# MX.net
KiCad netlist of a schematic drawn in Altium Designer
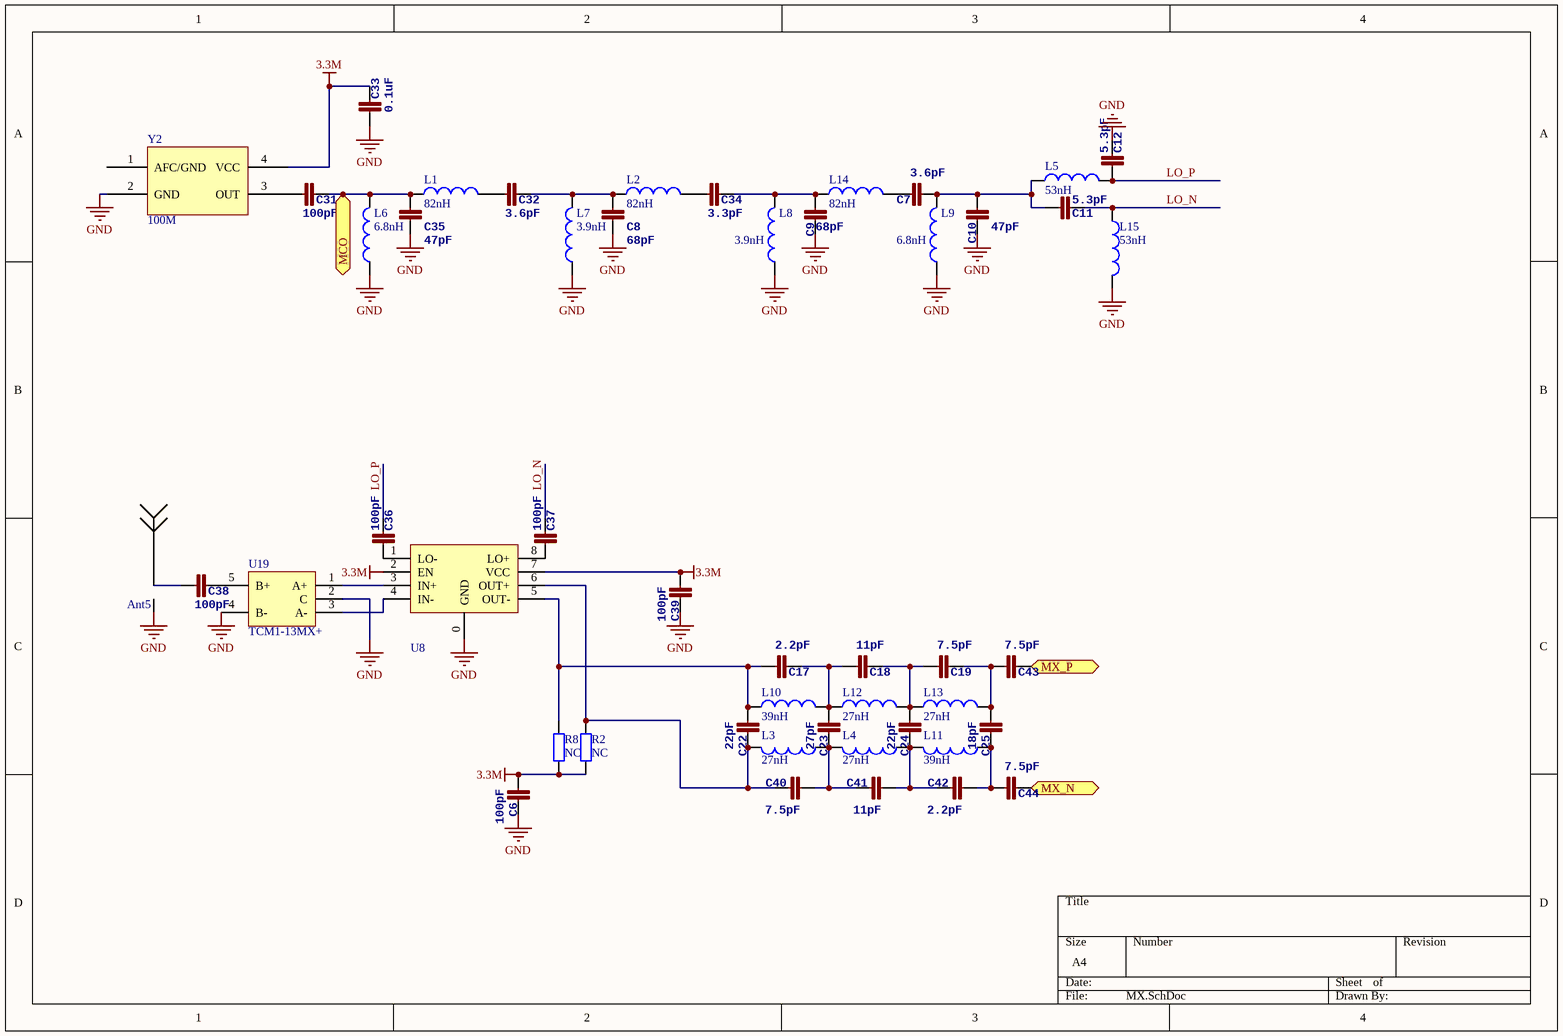
[diagram p0: MX.SchDoc]

(export (version "E")
  (design (tool "Eeschema 10.0.6"))
  (components
    (comp (ref "Ant5") (value "Antenna") (footprint "BK5811:SMA") (libsource (lib "F4SDR") (part "Antenna")))
    (comp (ref "C6")
      (value "100pF")
      (footprint "0402")
      (description "<b>Capacitor</b>\nStandard 0603 ceramic capacitor, and 0.1\" leaded capacitor.")
      (fields (field (name "PARTNO") "CC0402ZRY5V7BB104"))
      (libsource (lib "") (part "CAP0402-CAP_1"))
    )
    (comp (ref "C7")
      (value "3.6pF")
      (footprint "0402")
      (description "<b>Capacitor</b>\nStandard 0603 ceramic capacitor, and 0.1\" leaded capacitor.")
      (fields (field (name "PARTNO") "CC0402ZRY5V7BB104"))
      (libsource (lib "pixhawk2") (part "CAP0402-CAP"))
    )
    (comp (ref "C8")
      (value "68pF")
      (footprint "0402")
      (description "<b>Capacitor</b>\nStandard 0603 ceramic capacitor, and 0.1\" leaded capacitor.")
      (fields (field (name "PARTNO") "CC0402ZRY5V7BB104"))
      (libsource (lib "") (part "CAP0402-CAP_1"))
    )
    (comp (ref "C9")
      (value "68pF")
      (footprint "0402")
      (description "<b>Capacitor</b>\nStandard 0603 ceramic capacitor, and 0.1\" leaded capacitor.")
      (fields (field (name "PARTNO") "CC0402ZRY5V7BB104"))
      (libsource (lib "") (part "CAP0402-CAP_1"))
    )
    (comp (ref "C10")
      (value "47pF")
      (footprint "0402")
      (description "<b>Capacitor</b>\nStandard 0603 ceramic capacitor, and 0.1\" leaded capacitor.")
      (fields (field (name "PARTNO") "CC0402ZRY5V7BB104"))
      (libsource (lib "") (part "CAP0402-CAP_1"))
    )
    (comp (ref "C11")
      (value "5.3pF")
      (footprint "0402")
      (description "<b>Capacitor</b>\nStandard 0603 ceramic capacitor, and 0.1\" leaded capacitor.")
      (fields (field (name "PARTNO") "CC0402ZRY5V7BB104"))
      (libsource (lib "pixhawk2") (part "CAP0402-CAP"))
    )
    (comp (ref "C12")
      (value "5.3pF")
      (footprint "0402")
      (description "<b>Capacitor</b>\nStandard 0603 ceramic capacitor, and 0.1\" leaded capacitor.")
      (fields (field (name "PARTNO") "CC0402ZRY5V7BB104"))
      (libsource (lib "") (part "CAP0402-CAP_2"))
    )
    (comp (ref "C17")
      (value "2.2pF")
      (footprint "0402")
      (description "<b>Capacitor</b>\nStandard 0603 ceramic capacitor, and 0.1\" leaded capacitor.")
      (fields (field (name "PARTNO") "CC0402ZRY5V7BB104"))
      (libsource (lib "pixhawk2") (part "CAP0402-CAP"))
    )
    (comp (ref "C18")
      (value "11pF")
      (footprint "0402")
      (description "<b>Capacitor</b>\nStandard 0603 ceramic capacitor, and 0.1\" leaded capacitor.")
      (fields (field (name "PARTNO") "CC0402ZRY5V7BB104"))
      (libsource (lib "pixhawk2") (part "CAP0402-CAP"))
    )
    (comp (ref "C19")
      (value "7.5pF")
      (footprint "0402")
      (description "<b>Capacitor</b>\nStandard 0603 ceramic capacitor, and 0.1\" leaded capacitor.")
      (fields (field (name "PARTNO") "CC0402ZRY5V7BB104"))
      (libsource (lib "pixhawk2") (part "CAP0402-CAP"))
    )
    (comp (ref "C22")
      (value "22pF")
      (footprint "0402")
      (description "<b>Capacitor</b>\nStandard 0603 ceramic capacitor, and 0.1\" leaded capacitor.")
      (fields (field (name "PARTNO") "CC0402ZRY5V7BB104"))
      (libsource (lib "") (part "CAP0402-CAP_1"))
    )
    (comp (ref "C23")
      (value "27pF")
      (footprint "0402")
      (description "<b>Capacitor</b>\nStandard 0603 ceramic capacitor, and 0.1\" leaded capacitor.")
      (fields (field (name "PARTNO") "CC0402ZRY5V7BB104"))
      (libsource (lib "") (part "CAP0402-CAP_1"))
    )
    (comp (ref "C24")
      (value "22pF")
      (footprint "0402")
      (description "<b>Capacitor</b>\nStandard 0603 ceramic capacitor, and 0.1\" leaded capacitor.")
      (fields (field (name "PARTNO") "CC0402ZRY5V7BB104"))
      (libsource (lib "") (part "CAP0402-CAP_1"))
    )
    (comp (ref "C25")
      (value "18pF")
      (footprint "0402")
      (description "<b>Capacitor</b>\nStandard 0603 ceramic capacitor, and 0.1\" leaded capacitor.")
      (fields (field (name "PARTNO") "CC0402ZRY5V7BB104"))
      (libsource (lib "") (part "CAP0402-CAP_1"))
    )
    (comp (ref "C31")
      (value "100pF")
      (footprint "0402")
      (description "<b>Capacitor</b>\nStandard 0603 ceramic capacitor, and 0.1\" leaded capacitor.")
      (fields (field (name "PARTNO") "CC0402ZRY5V7BB104"))
      (libsource (lib "pixhawk2") (part "CAP0402-CAP"))
    )
    (comp (ref "C32")
      (value "3.6pF")
      (footprint "0402")
      (description "<b>Capacitor</b>\nStandard 0603 ceramic capacitor, and 0.1\" leaded capacitor.")
      (fields (field (name "PARTNO") "CC0402ZRY5V7BB104"))
      (libsource (lib "pixhawk2") (part "CAP0402-CAP"))
    )
    (comp (ref "C33")
      (value "0.1uF")
      (footprint "0402")
      (description "<b>Capacitor</b>\nStandard 0603 ceramic capacitor, and 0.1\" leaded capacitor.")
      (fields (field (name "PARTNO") "CC0402ZRY5V7BB104"))
      (libsource (lib "") (part "CAP0402-CAP_2"))
    )
    (comp (ref "C34")
      (value "3.3pF")
      (footprint "0402")
      (description "<b>Capacitor</b>\nStandard 0603 ceramic capacitor, and 0.1\" leaded capacitor.")
      (fields (field (name "PARTNO") "CC0402ZRY5V7BB104"))
      (libsource (lib "pixhawk2") (part "CAP0402-CAP"))
    )
    (comp (ref "C35")
      (value "47pF")
      (footprint "0402")
      (description "<b>Capacitor</b>\nStandard 0603 ceramic capacitor, and 0.1\" leaded capacitor.")
      (fields (field (name "PARTNO") "CC0402ZRY5V7BB104"))
      (libsource (lib "") (part "CAP0402-CAP_1"))
    )
    (comp (ref "C36")
      (value "100pF")
      (footprint "0402")
      (description "<b>Capacitor</b>\nStandard 0603 ceramic capacitor, and 0.1\" leaded capacitor.")
      (fields (field (name "PARTNO") "CC0402ZRY5V7BB104"))
      (libsource (lib "") (part "CAP0402-CAP_2"))
    )
    (comp (ref "C37")
      (value "100pF")
      (footprint "0402")
      (description "<b>Capacitor</b>\nStandard 0603 ceramic capacitor, and 0.1\" leaded capacitor.")
      (fields (field (name "PARTNO") "CC0402ZRY5V7BB104"))
      (libsource (lib "") (part "CAP0402-CAP_2"))
    )
    (comp (ref "C38")
      (value "100pF")
      (footprint "0402")
      (description "<b>Capacitor</b>\nStandard 0603 ceramic capacitor, and 0.1\" leaded capacitor.")
      (fields (field (name "PARTNO") "CC0402ZRY5V7BB104"))
      (libsource (lib "pixhawk2") (part "CAP0402-CAP"))
    )
    (comp (ref "C39")
      (value "100pF")
      (footprint "0402")
      (description "<b>Capacitor</b>\nStandard 0603 ceramic capacitor, and 0.1\" leaded capacitor.")
      (fields (field (name "PARTNO") "CC0402ZRY5V7BB104"))
      (libsource (lib "") (part "CAP0402-CAP_1"))
    )
    (comp (ref "C40")
      (value "7.5pF")
      (footprint "0402")
      (description "<b>Capacitor</b>\nStandard 0603 ceramic capacitor, and 0.1\" leaded capacitor.")
      (fields (field (name "PARTNO") "CC0402ZRY5V7BB104"))
      (libsource (lib "") (part "CAP0402-CAP_3"))
    )
    (comp (ref "C41")
      (value "11pF")
      (footprint "0402")
      (description "<b>Capacitor</b>\nStandard 0603 ceramic capacitor, and 0.1\" leaded capacitor.")
      (fields (field (name "PARTNO") "CC0402ZRY5V7BB104"))
      (libsource (lib "") (part "CAP0402-CAP_3"))
    )
    (comp (ref "C42")
      (value "2.2pF")
      (footprint "0402")
      (description "<b>Capacitor</b>\nStandard 0603 ceramic capacitor, and 0.1\" leaded capacitor.")
      (fields (field (name "PARTNO") "CC0402ZRY5V7BB104"))
      (libsource (lib "") (part "CAP0402-CAP_3"))
    )
    (comp (ref "C43")
      (value "7.5pF")
      (footprint "0402")
      (description "<b>Capacitor</b>\nStandard 0603 ceramic capacitor, and 0.1\" leaded capacitor.")
      (fields (field (name "PARTNO") "CC0402ZRY5V7BB104"))
      (libsource (lib "pixhawk2") (part "CAP0402-CAP"))
    )
    (comp (ref "C44")
      (value "7.5pF")
      (footprint "0402")
      (description "<b>Capacitor</b>\nStandard 0603 ceramic capacitor, and 0.1\" leaded capacitor.")
      (fields (field (name "PARTNO") "CC0402ZRY5V7BB104"))
      (libsource (lib "pixhawk2") (part "CAP0402-CAP"))
    )
    (comp (ref "L1")
      (value "82nH")
      (footprint "0402")
      (description "Inductor")
      (fields (field (name "PUBLISHER") "Altium Limited"))
      (libsource (lib "Miscellaneous Devices") (part "Inductor"))
    )
    (comp (ref "L2")
      (value "82nH")
      (footprint "0402")
      (description "Inductor")
      (fields (field (name "PUBLISHER") "Altium Limited"))
      (libsource (lib "Miscellaneous Devices") (part "Inductor"))
    )
    (comp (ref "L3")
      (value "27nH")
      (footprint "0402")
      (description "Inductor")
      (fields (field (name "PUBLISHER") "Altium Limited"))
      (libsource (lib "Miscellaneous Devices") (part "Inductor"))
    )
    (comp (ref "L4")
      (value "27nH")
      (footprint "0402")
      (description "Inductor")
      (fields (field (name "PUBLISHER") "Altium Limited"))
      (libsource (lib "Miscellaneous Devices") (part "Inductor"))
    )
    (comp (ref "L5")
      (value "53nH")
      (footprint "0402")
      (description "Inductor")
      (fields (field (name "PUBLISHER") "Altium Limited"))
      (libsource (lib "Miscellaneous Devices") (part "Inductor"))
    )
    (comp (ref "L6")
      (value "6.8nH")
      (footprint "0402")
      (description "Inductor")
      (fields (field (name "PUBLISHER") "Altium Limited"))
      (libsource (lib "Miscellaneous Devices") (part "Inductor"))
    )
    (comp (ref "L7")
      (value "3.9nH")
      (footprint "0402")
      (description "Inductor")
      (fields (field (name "PUBLISHER") "Altium Limited"))
      (libsource (lib "Miscellaneous Devices") (part "Inductor"))
    )
    (comp (ref "L8")
      (value "3.9nH")
      (footprint "0402")
      (description "Inductor")
      (fields (field (name "PUBLISHER") "Altium Limited"))
      (libsource (lib "Miscellaneous Devices") (part "Inductor"))
    )
    (comp (ref "L9")
      (value "6.8nH")
      (footprint "0402")
      (description "Inductor")
      (fields (field (name "PUBLISHER") "Altium Limited"))
      (libsource (lib "Miscellaneous Devices") (part "Inductor"))
    )
    (comp (ref "L10")
      (value "39nH")
      (footprint "0402")
      (description "Inductor")
      (fields (field (name "PUBLISHER") "Altium Limited"))
      (libsource (lib "Miscellaneous Devices") (part "Inductor"))
    )
    (comp (ref "L11")
      (value "39nH")
      (footprint "0402")
      (description "Inductor")
      (fields (field (name "PUBLISHER") "Altium Limited"))
      (libsource (lib "Miscellaneous Devices") (part "Inductor"))
    )
    (comp (ref "L12")
      (value "27nH")
      (footprint "0402")
      (description "Inductor")
      (fields (field (name "PUBLISHER") "Altium Limited"))
      (libsource (lib "Miscellaneous Devices") (part "Inductor"))
    )
    (comp (ref "L13")
      (value "27nH")
      (footprint "0402")
      (description "Inductor")
      (fields (field (name "PUBLISHER") "Altium Limited"))
      (libsource (lib "Miscellaneous Devices") (part "Inductor"))
    )
    (comp (ref "L14")
      (value "82nH")
      (footprint "0402")
      (description "Inductor")
      (fields (field (name "PUBLISHER") "Altium Limited"))
      (libsource (lib "Miscellaneous Devices") (part "Inductor"))
    )
    (comp (ref "L15")
      (value "53nH")
      (footprint "0402")
      (description "Inductor")
      (fields (field (name "PUBLISHER") "Altium Limited"))
      (libsource (lib "Miscellaneous Devices") (part "Inductor"))
    )
    (comp (ref "R2")
      (value "NC")
      (footprint "0402")
      (description "Resistor")
      (fields (field (name "PUBLISHER") "Altium Limited"))
      (libsource (lib "Miscellaneous Devices") (part "Res2"))
    )
    (comp (ref "R8")
      (value "NC")
      (footprint "0402")
      (description "Resistor")
      (fields (field (name "PUBLISHER") "Altium Limited"))
      (libsource (lib "Miscellaneous Devices") (part "Res2"))
    )
    (comp (ref "U8") (value "LT5560") (footprint "LT5560") (libsource (lib "F4SDR") (part "LT5560")))
    (comp (ref "U19")
      (value "TCM1-13MX+")
      (footprint "TCM-13M+")
      (libsource (lib "F4SDR") (part "TCM1-1-13M+"))
    )
    (comp (ref "Y2") (value "100M") (footprint "TXC_7Q") (libsource (lib "F4SDR") (part "OSC_40M")))
  )
  (nets
    (net (code "1") (name "/LO_N") (class "Default")
      (node (ref "C11") (pin "2") (pinfunction "2_2") (pintype "passive"))
      (node (ref "C37") (pin "2") (pinfunction "2_2") (pintype "passive"))
      (node (ref "L15") (pin "1") (pinfunction "1_1") (pintype "passive"))
    )
    (net (code "2") (name "/LO_P") (class "Default")
      (node (ref "C12") (pin "1") (pinfunction "1_1") (pintype "passive"))
      (node (ref "C36") (pin "2") (pinfunction "2_2") (pintype "passive"))
      (node (ref "L5") (pin "2") (pinfunction "2_2") (pintype "passive"))
    )
    (net (code "3") (name "/MCO") (class "Default")
      (node (ref "C31") (pin "2") (pinfunction "2_2") (pintype "passive"))
      (node (ref "C35") (pin "1") (pinfunction "1_1") (pintype "passive"))
      (node (ref "L1") (pin "1") (pinfunction "1_1") (pintype "passive"))
      (node (ref "L6") (pin "2") (pinfunction "2_2") (pintype "passive"))
    )
    (net (code "4") (name "/MX_N") (class "Default")
      (node (ref "C44") (pin "2") (pinfunction "2_2") (pintype "passive"))
    )
    (net (code "5") (name "/MX_P") (class "Default")
      (node (ref "C43") (pin "2") (pinfunction "2_2") (pintype "passive"))
    )
    (net (code "6") (name "3.3M") (class "Default")
      (node (ref "C33") (pin "2") (pinfunction "2_2") (pintype "passive"))
      (node (ref "C39") (pin "1") (pinfunction "1_1") (pintype "passive"))
      (node (ref "C6") (pin "1") (pinfunction "1_1") (pintype "passive"))
      (node (ref "R2") (pin "2") (pinfunction "2_2") (pintype "passive"))
      (node (ref "R8") (pin "2") (pinfunction "2_2") (pintype "passive"))
      (node (ref "U8") (pin "2") (pinfunction "EN_2") (pintype "passive"))
      (node (ref "U8") (pin "7") (pinfunction "VCC_7") (pintype "passive"))
      (node (ref "Y2") (pin "4") (pinfunction "VCC_4") (pintype "passive"))
    )
    (net (code "7") (name "GND") (class "Default")
      (node (ref "Ant5") (pin "GND") (pinfunction "G_GND") (pintype "passive"))
      (node (ref "C10") (pin "2") (pinfunction "2_2") (pintype "passive"))
      (node (ref "C12") (pin "2") (pinfunction "2_2") (pintype "passive"))
      (node (ref "C33") (pin "1") (pinfunction "1_1") (pintype "passive"))
      (node (ref "C35") (pin "2") (pinfunction "2_2") (pintype "passive"))
      (node (ref "C39") (pin "2") (pinfunction "2_2") (pintype "passive"))
      (node (ref "C6") (pin "2") (pinfunction "2_2") (pintype "passive"))
      (node (ref "C8") (pin "2") (pinfunction "2_2") (pintype "passive"))
      (node (ref "C9") (pin "2") (pinfunction "2_2") (pintype "passive"))
      (node (ref "L15") (pin "2") (pinfunction "2_2") (pintype "passive"))
      (node (ref "L6") (pin "1") (pinfunction "1_1") (pintype "passive"))
      (node (ref "L7") (pin "1") (pinfunction "1_1") (pintype "passive"))
      (node (ref "L8") (pin "1") (pinfunction "1_1") (pintype "passive"))
      (node (ref "L9") (pin "1") (pinfunction "1_1") (pintype "passive"))
      (node (ref "U19") (pin "2") (pinfunction "C_2") (pintype "passive"))
      (node (ref "U19") (pin "4") (pinfunction "B-_4") (pintype "passive"))
      (node (ref "U8") (pin "0") (pinfunction "GND_0") (pintype "passive"))
      (node (ref "Y2") (pin "2") (pinfunction "GND_2") (pintype "passive"))
    )
    (net (code "8") (name "Net-(Ant5-Pad1)") (class "Default")
      (node (ref "Ant5") (pin "1") (pinfunction "1_1") (pintype "passive"))
      (node (ref "C38") (pin "1") (pinfunction "1_1") (pintype "passive"))
    )
    (net (code "9") (name "Net-(C7-Pad1)") (class "Default")
      (node (ref "C7") (pin "1") (pinfunction "1_1") (pintype "passive"))
      (node (ref "L14") (pin "2") (pinfunction "2_2") (pintype "passive"))
    )
    (net (code "10") (name "Net-(C10-Pad1)") (class "Default")
      (node (ref "C10") (pin "1") (pinfunction "1_1") (pintype "passive"))
      (node (ref "C11") (pin "1") (pinfunction "1_1") (pintype "passive"))
      (node (ref "C7") (pin "2") (pinfunction "2_2") (pintype "passive"))
      (node (ref "L5") (pin "1") (pinfunction "1_1") (pintype "passive"))
      (node (ref "L9") (pin "2") (pinfunction "2_2") (pintype "passive"))
    )
    (net (code "11") (name "Net-(C17-Pad2)") (class "Default")
      (node (ref "C17") (pin "2") (pinfunction "2_2") (pintype "passive"))
      (node (ref "C18") (pin "1") (pinfunction "1_1") (pintype "passive"))
      (node (ref "C23") (pin "1") (pinfunction "1_1") (pintype "passive"))
      (node (ref "L10") (pin "2") (pinfunction "2_2") (pintype "passive"))
      (node (ref "L12") (pin "1") (pinfunction "1_1") (pintype "passive"))
    )
    (net (code "12") (name "Net-(C18-Pad2)") (class "Default")
      (node (ref "C18") (pin "2") (pinfunction "2_2") (pintype "passive"))
      (node (ref "C19") (pin "1") (pinfunction "1_1") (pintype "passive"))
      (node (ref "C24") (pin "1") (pinfunction "1_1") (pintype "passive"))
      (node (ref "L12") (pin "2") (pinfunction "2_2") (pintype "passive"))
      (node (ref "L13") (pin "1") (pinfunction "1_1") (pintype "passive"))
    )
    (net (code "13") (name "Net-(C19-Pad2)") (class "Default")
      (node (ref "C19") (pin "2") (pinfunction "2_2") (pintype "passive"))
      (node (ref "C25") (pin "1") (pinfunction "1_1") (pintype "passive"))
      (node (ref "C43") (pin "1") (pinfunction "1_1") (pintype "passive"))
      (node (ref "L13") (pin "2") (pinfunction "2_2") (pintype "passive"))
    )
    (net (code "14") (name "Net-(C23-Pad2)") (class "Default")
      (node (ref "C23") (pin "2") (pinfunction "2_2") (pintype "passive"))
      (node (ref "C40") (pin "1") (pinfunction "1_1") (pintype "passive"))
      (node (ref "C41") (pin "2") (pinfunction "2_2") (pintype "passive"))
      (node (ref "L3") (pin "1") (pinfunction "1_1") (pintype "passive"))
      (node (ref "L4") (pin "2") (pinfunction "2_2") (pintype "passive"))
    )
    (net (code "15") (name "Net-(C24-Pad2)") (class "Default")
      (node (ref "C24") (pin "2") (pinfunction "2_2") (pintype "passive"))
      (node (ref "C41") (pin "1") (pinfunction "1_1") (pintype "passive"))
      (node (ref "C42") (pin "2") (pinfunction "2_2") (pintype "passive"))
      (node (ref "L11") (pin "2") (pinfunction "2_2") (pintype "passive"))
      (node (ref "L4") (pin "1") (pinfunction "1_1") (pintype "passive"))
    )
    (net (code "16") (name "Net-(C25-Pad2)") (class "Default")
      (node (ref "C25") (pin "2") (pinfunction "2_2") (pintype "passive"))
      (node (ref "C42") (pin "1") (pinfunction "1_1") (pintype "passive"))
      (node (ref "C44") (pin "1") (pinfunction "1_1") (pintype "passive"))
      (node (ref "L11") (pin "1") (pinfunction "1_1") (pintype "passive"))
    )
    (net (code "17") (name "Net-(C32-Pad1)") (class "Default")
      (node (ref "C32") (pin "1") (pinfunction "1_1") (pintype "passive"))
      (node (ref "L1") (pin "2") (pinfunction "2_2") (pintype "passive"))
    )
    (net (code "18") (name "Net-(C32-Pad2)") (class "Default")
      (node (ref "C32") (pin "2") (pinfunction "2_2") (pintype "passive"))
      (node (ref "C8") (pin "1") (pinfunction "1_1") (pintype "passive"))
      (node (ref "L2") (pin "1") (pinfunction "1_1") (pintype "passive"))
      (node (ref "L7") (pin "2") (pinfunction "2_2") (pintype "passive"))
    )
    (net (code "19") (name "Net-(C34-Pad1)") (class "Default")
      (node (ref "C34") (pin "1") (pinfunction "1_1") (pintype "passive"))
      (node (ref "L2") (pin "2") (pinfunction "2_2") (pintype "passive"))
    )
    (net (code "20") (name "Net-(C34-Pad2)") (class "Default")
      (node (ref "C34") (pin "2") (pinfunction "2_2") (pintype "passive"))
      (node (ref "C9") (pin "1") (pinfunction "1_1") (pintype "passive"))
      (node (ref "L14") (pin "1") (pinfunction "1_1") (pintype "passive"))
      (node (ref "L8") (pin "2") (pinfunction "2_2") (pintype "passive"))
    )
    (net (code "21") (name "Net-(U8-LO+)") (class "Default")
      (node (ref "C37") (pin "1") (pinfunction "1_1") (pintype "passive"))
      (node (ref "U8") (pin "8") (pinfunction "LO+_8") (pintype "passive"))
    )
    (net (code "22") (name "Net-(U8-LO-)") (class "Default")
      (node (ref "C36") (pin "1") (pinfunction "1_1") (pintype "passive"))
      (node (ref "U8") (pin "1") (pinfunction "LO-_1") (pintype "passive"))
    )
    (net (code "23") (name "Net-(U8-OUT+)") (class "Default")
      (node (ref "C22") (pin "2") (pinfunction "2_2") (pintype "passive"))
      (node (ref "C40") (pin "2") (pinfunction "2_2") (pintype "passive"))
      (node (ref "L3") (pin "2") (pinfunction "2_2") (pintype "passive"))
      (node (ref "R2") (pin "1") (pinfunction "1_1") (pintype "passive"))
      (node (ref "U8") (pin "6") (pinfunction "OUT+_6") (pintype "passive"))
    )
    (net (code "24") (name "Net-(U8-OUT-)") (class "Default")
      (node (ref "C17") (pin "1") (pinfunction "1_1") (pintype "passive"))
      (node (ref "C22") (pin "1") (pinfunction "1_1") (pintype "passive"))
      (node (ref "L10") (pin "1") (pinfunction "1_1") (pintype "passive"))
      (node (ref "R8") (pin "1") (pinfunction "1_1") (pintype "passive"))
      (node (ref "U8") (pin "5") (pinfunction "OUT-_5") (pintype "passive"))
    )
    (net (code "25") (name "Net-(U19-A+)") (class "Default")
      (node (ref "U19") (pin "1") (pinfunction "A+_1") (pintype "passive"))
      (node (ref "U8") (pin "3") (pinfunction "IN+_3") (pintype "passive"))
    )
    (net (code "26") (name "Net-(U19-A-)") (class "Default")
      (node (ref "U19") (pin "3") (pinfunction "A-_3") (pintype "passive"))
      (node (ref "U8") (pin "4") (pinfunction "IN-_4") (pintype "passive"))
    )
    (net (code "27") (name "Net-(U19-B+)") (class "Default")
      (node (ref "C38") (pin "2") (pinfunction "2_2") (pintype "passive"))
      (node (ref "U19") (pin "5") (pinfunction "B+_5") (pintype "passive"))
    )
    (net (code "28") (name "Net-(Y2-OUT)") (class "Default")
      (node (ref "C31") (pin "1") (pinfunction "1_1") (pintype "passive"))
      (node (ref "Y2") (pin "3") (pinfunction "OUT_3") (pintype "passive"))
    )
    (net (code "29") (name "unconnected-(Y2-AFC{slash}GND-Pad1)") (class "Default")
      (node (ref "Y2") (pin "1") (pinfunction "AFC/GND_1") (pintype "passive"))
    )
  )
)
